# final_header.net
KiCad netlist of a schematic drawn in EAGLE
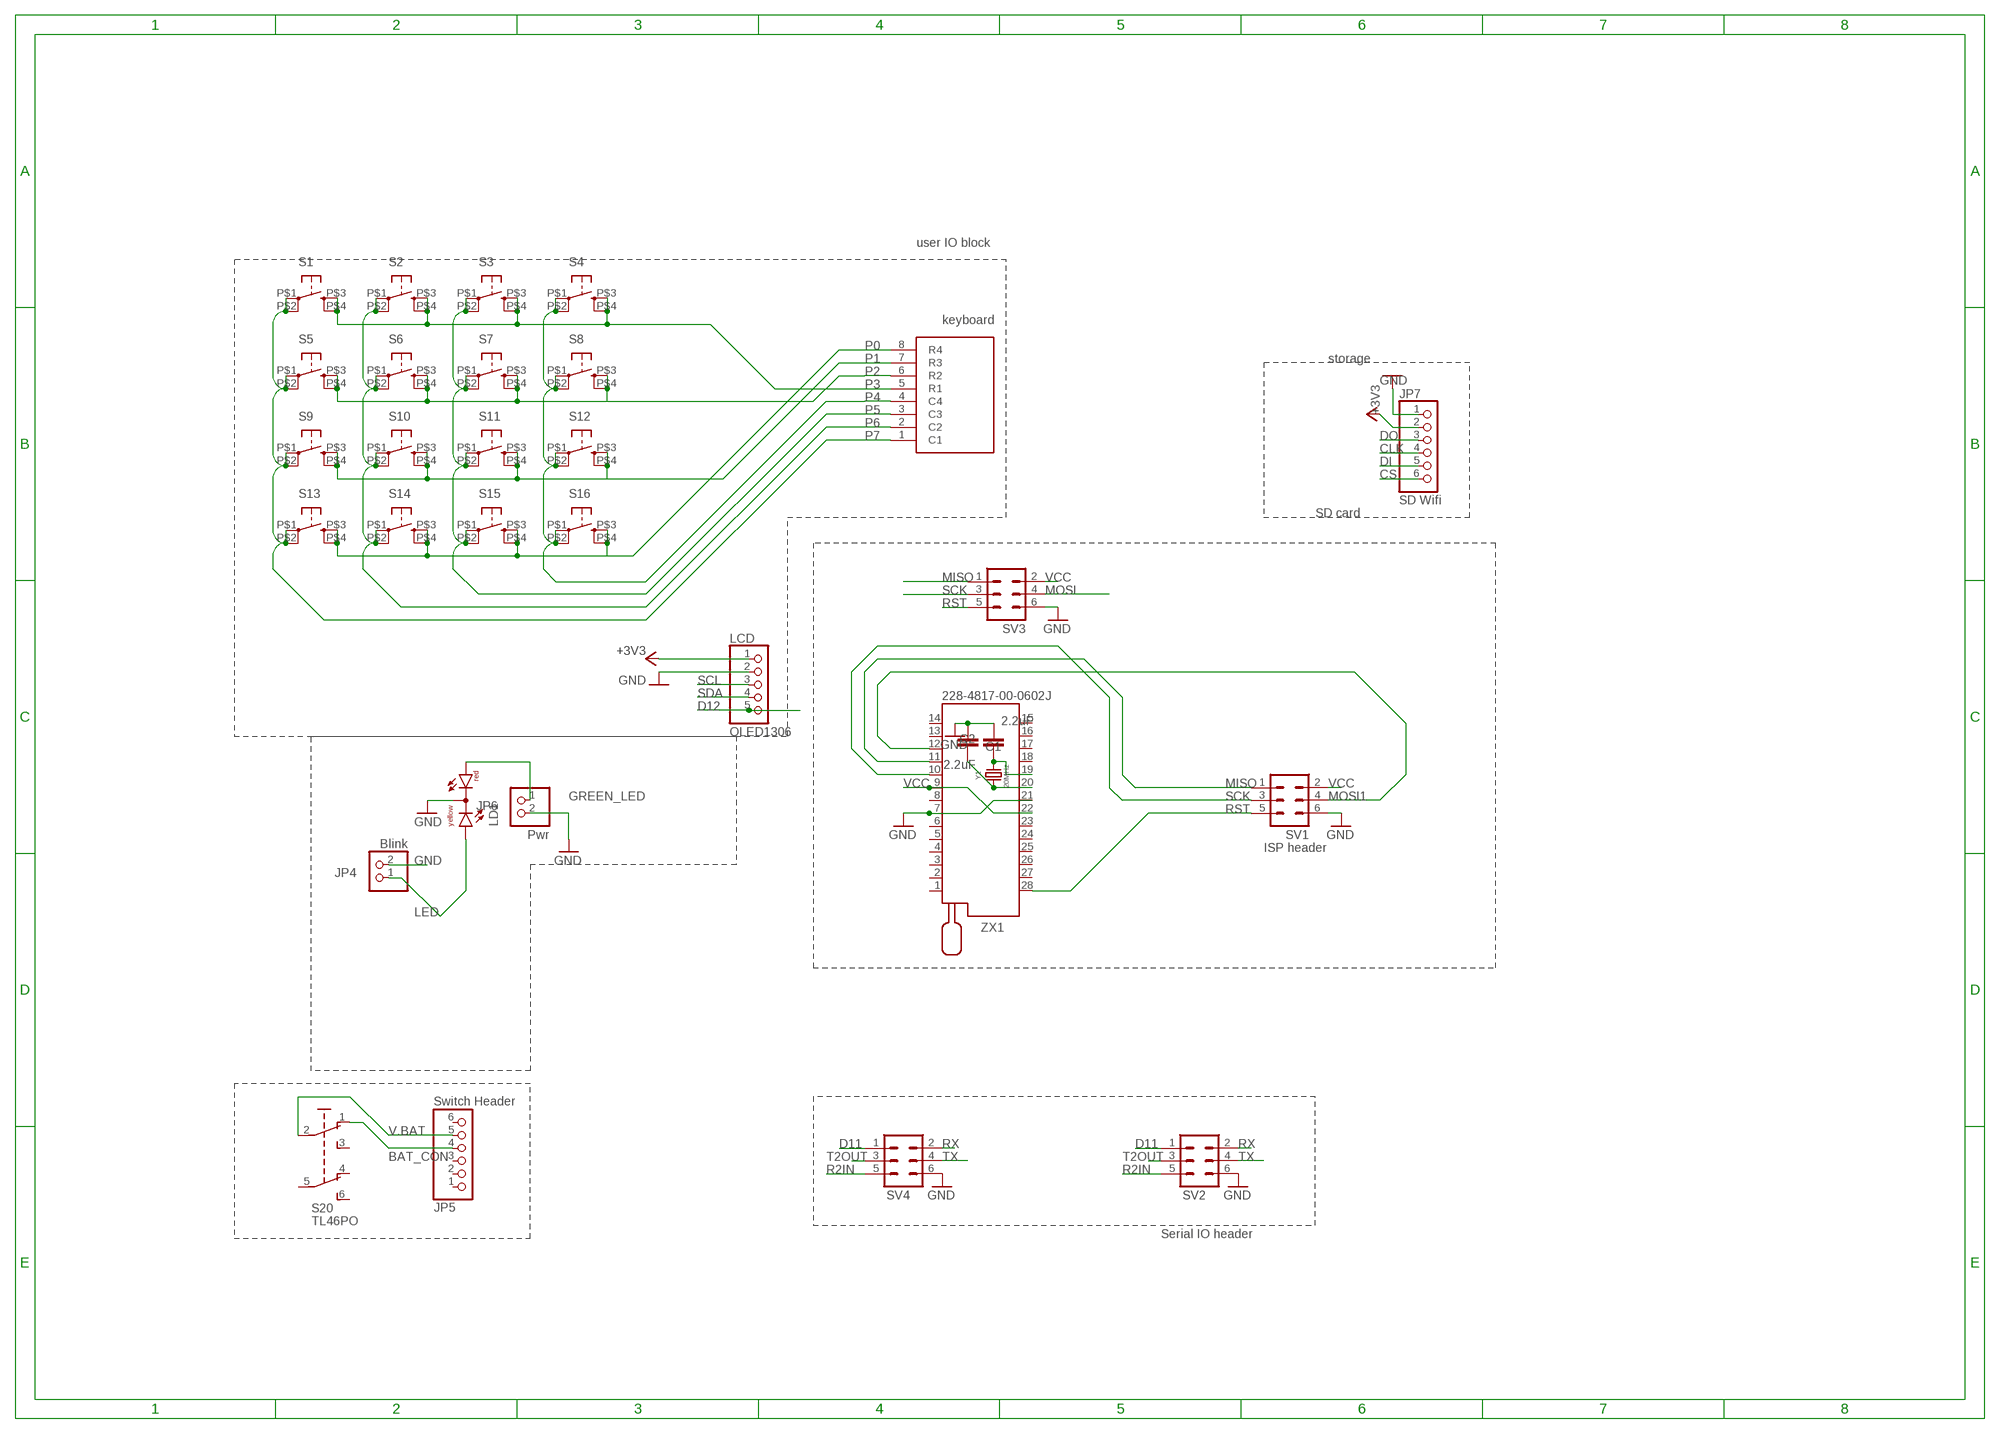
[diagram p0: schematic, sheet 1]

(export (version "E")
  (design (tool "Eeschema 10.0.6"))
  (components
    (comp (ref "C1")
      (value "2.2uF")
      (footprint "eagle-import:1206")
      (libsource (lib "eagle-import") (part "2.2UF-1206-50V-10%"))
    )
    (comp (ref "C2")
      (value "2.2uF")
      (footprint "eagle-import:1206")
      (libsource (lib "eagle-import") (part "2.2UF-1206-50V-10%"))
    )
    (comp (ref "JP4")
      (value "Blink")
      (footprint "eagle-import:1X02")
      (libsource (lib "eagle-import") (part "PINHD-1X2"))
    )
    (comp (ref "JP5")
      (value "Switch Header")
      (footprint "eagle-import:1X06")
      (libsource (lib "eagle-import") (part "PINHD-1X6"))
    )
    (comp (ref "JP6")
      (value "Pwr")
      (footprint "eagle-import:1X02")
      (libsource (lib "eagle-import") (part "PINHD-1X2"))
    )
    (comp (ref "JP7")
      (value "SD Wifi")
      (footprint "eagle-import:1X06")
      (libsource (lib "eagle-import") (part "PINHD-1X6"))
    )
    (comp (ref "LCD")
      (value "OLED1306")
      (footprint "eagle-import:1X05")
      (libsource (lib "eagle-import") (part "PINHD-1X5"))
    )
    (comp (ref "LD1")
      (value "DUOLED-RY-C")
      (footprint "eagle-import:DUOLED-C-5MM")
      (libsource (lib "eagle-import") (part "DUOLED-RY-C"))
    )
    (comp (ref "S1")
      (value "10-XX-SMD")
      (footprint "eagle-import:B3F-10XX-SMD")
      (libsource (lib "eagle-import") (part "10-XX-SMD"))
    )
    (comp (ref "S2")
      (value "10-XX-SMD")
      (footprint "eagle-import:B3F-10XX-SMD")
      (libsource (lib "eagle-import") (part "10-XX-SMD"))
    )
    (comp (ref "S3")
      (value "10-XX-SMD")
      (footprint "eagle-import:B3F-10XX-SMD")
      (libsource (lib "eagle-import") (part "10-XX-SMD"))
    )
    (comp (ref "S4")
      (value "10-XX-SMD")
      (footprint "eagle-import:B3F-10XX-SMD")
      (libsource (lib "eagle-import") (part "10-XX-SMD"))
    )
    (comp (ref "S5")
      (value "10-XX-SMD")
      (footprint "eagle-import:B3F-10XX-SMD")
      (libsource (lib "eagle-import") (part "10-XX-SMD"))
    )
    (comp (ref "S6")
      (value "10-XX-SMD")
      (footprint "eagle-import:B3F-10XX-SMD")
      (libsource (lib "eagle-import") (part "10-XX-SMD"))
    )
    (comp (ref "S7")
      (value "10-XX-SMD")
      (footprint "eagle-import:B3F-10XX-SMD")
      (libsource (lib "eagle-import") (part "10-XX-SMD"))
    )
    (comp (ref "S8")
      (value "10-XX-SMD")
      (footprint "eagle-import:B3F-10XX-SMD")
      (libsource (lib "eagle-import") (part "10-XX-SMD"))
    )
    (comp (ref "S9")
      (value "10-XX-SMD")
      (footprint "eagle-import:B3F-10XX-SMD")
      (libsource (lib "eagle-import") (part "10-XX-SMD"))
    )
    (comp (ref "S10")
      (value "10-XX-SMD")
      (footprint "eagle-import:B3F-10XX-SMD")
      (libsource (lib "eagle-import") (part "10-XX-SMD"))
    )
    (comp (ref "S11")
      (value "10-XX-SMD")
      (footprint "eagle-import:B3F-10XX-SMD")
      (libsource (lib "eagle-import") (part "10-XX-SMD"))
    )
    (comp (ref "S12")
      (value "10-XX-SMD")
      (footprint "eagle-import:B3F-10XX-SMD")
      (libsource (lib "eagle-import") (part "10-XX-SMD"))
    )
    (comp (ref "S13")
      (value "10-XX-SMD")
      (footprint "eagle-import:B3F-10XX-SMD")
      (libsource (lib "eagle-import") (part "10-XX-SMD"))
    )
    (comp (ref "S14")
      (value "10-XX-SMD")
      (footprint "eagle-import:B3F-10XX-SMD")
      (libsource (lib "eagle-import") (part "10-XX-SMD"))
    )
    (comp (ref "S15")
      (value "10-XX-SMD")
      (footprint "eagle-import:B3F-10XX-SMD")
      (libsource (lib "eagle-import") (part "10-XX-SMD"))
    )
    (comp (ref "S16")
      (value "10-XX-SMD")
      (footprint "eagle-import:B3F-10XX-SMD")
      (libsource (lib "eagle-import") (part "10-XX-SMD"))
    )
    (comp (ref "S20")
      (value "TL46PO")
      (footprint "eagle-import:TL4XPO")
      (libsource (lib "eagle-import") (part "TL46PO"))
    )
    (comp (ref "SV1")
      (value "ML6")
      (footprint "eagle-import:ML6")
      (libsource (lib "eagle-import") (part "ML6"))
    )
    (comp (ref "SV2")
      (value "ML6")
      (footprint "eagle-import:ML6")
      (libsource (lib "eagle-import") (part "ML6"))
    )
    (comp (ref "SV3")
      (value "ML6")
      (footprint "eagle-import:ML6")
      (libsource (lib "eagle-import") (part "ML6"))
    )
    (comp (ref "SV4")
      (value "ML6")
      (footprint "eagle-import:ML6")
      (libsource (lib "eagle-import") (part "ML6"))
    )
    (comp (ref "U$7")
      (value "KB1604")
      (footprint "eagle-import:KB1604")
      (libsource (lib "eagle-import") (part "KB1604"))
    )
    (comp (ref "Y1")
      (value "20MHz")
      (footprint "eagle-import:WE-XTAL_HC49_4HSMX")
      (fields (field (name "TOLERANCE") "±10ppm"))
      (libsource (lib "eagle-import") (part "WE-XTAL_HC49/4HSMX_830061856"))
    )
    (comp (ref "ZX1")
      (value "228-4817-00-0602J")
      (footprint "eagle-import:228-4817-00-0602J")
      (fields (field (name "MF") "3M"))
      (libsource (lib "eagle-import") (part "228-?00-0602J4817-"))
    )
  )
  (nets
    (net (code "1") (name "+3V3") (class "Default")
      (node (ref "JP7") (pin "2") (pinfunction "2_2") (pintype "passive"))
      (node (ref "LCD") (pin "1") (pinfunction "1_1") (pintype "passive"))
    )
    (net (code "2") (name "/BAT_CON") (class "Default")
      (node (ref "JP5") (pin "4") (pinfunction "4_4") (pintype "passive"))
      (node (ref "S20") (pin "1") (pinfunction "O_1") (pintype "passive"))
    )
    (net (code "3") (name "/CLK") (class "Default")
      (node (ref "JP7") (pin "4") (pinfunction "4_4") (pintype "passive"))
    )
    (net (code "4") (name "/CS") (class "Default")
      (node (ref "JP7") (pin "6") (pinfunction "6_6") (pintype "passive"))
    )
    (net (code "5") (name "/D11") (class "Default")
      (node (ref "SV2") (pin "1") (pinfunction "1_1") (pintype "passive"))
      (node (ref "SV4") (pin "1") (pinfunction "1_1") (pintype "passive"))
    )
    (net (code "6") (name "/D12") (class "Default")
      (node (ref "LCD") (pin "5") (pinfunction "5_5") (pintype "passive"))
    )
    (net (code "7") (name "/DI") (class "Default")
      (node (ref "JP7") (pin "5") (pinfunction "5_5") (pintype "passive"))
    )
    (net (code "8") (name "/DO") (class "Default")
      (node (ref "JP7") (pin "3") (pinfunction "3_3") (pintype "passive"))
    )
    (net (code "9") (name "/GREEN_LED") (class "Default")
      (node (ref "JP6") (pin "1") (pinfunction "1_1") (pintype "passive"))
      (node (ref "LD1") (pin "AR") (pinfunction "AR_AR") (pintype "passive"))
    )
    (net (code "10") (name "/LED") (class "Default")
      (node (ref "JP4") (pin "1") (pinfunction "1_1") (pintype "passive"))
      (node (ref "LD1") (pin "AX") (pinfunction "AY_AX") (pintype "passive"))
    )
    (net (code "11") (name "/MISO") (class "Default")
      (node (ref "SV1") (pin "1") (pinfunction "1_1") (pintype "passive"))
      (node (ref "SV3") (pin "1") (pinfunction "1_1") (pintype "passive"))
      (node (ref "ZX1") (pin "11") (pinfunction "11_11") (pintype "passive"))
    )
    (net (code "12") (name "/MOSI") (class "Default")
      (node (ref "SV3") (pin "4") (pinfunction "4_4") (pintype "passive"))
    )
    (net (code "13") (name "/MOSI1") (class "Default")
      (node (ref "SV1") (pin "4") (pinfunction "4_4") (pintype "passive"))
      (node (ref "ZX1") (pin "12") (pinfunction "12_12") (pintype "passive"))
    )
    (net (code "14") (name "/P0") (class "Default")
      (node (ref "S13") (pin "P$3") (pinfunction "S_P$3") (pintype "passive"))
      (node (ref "S13") (pin "P$4") (pinfunction "S1_P$4") (pintype "passive"))
      (node (ref "S14") (pin "P$3") (pinfunction "S_P$3") (pintype "passive"))
      (node (ref "S14") (pin "P$4") (pinfunction "S1_P$4") (pintype "passive"))
      (node (ref "S15") (pin "P$3") (pinfunction "S_P$3") (pintype "passive"))
      (node (ref "S15") (pin "P$4") (pinfunction "S1_P$4") (pintype "passive"))
      (node (ref "S16") (pin "P$3") (pinfunction "S_P$3") (pintype "passive"))
      (node (ref "S16") (pin "P$4") (pinfunction "S1_P$4") (pintype "passive"))
      (node (ref "U$7") (pin "8") (pinfunction "R4_8") (pintype "bidirectional"))
    )
    (net (code "15") (name "/P1") (class "Default")
      (node (ref "U$7") (pin "7") (pinfunction "R3_7") (pintype "bidirectional"))
    )
    (net (code "16") (name "/P2") (class "Default")
      (node (ref "S5") (pin "P$3") (pinfunction "S_P$3") (pintype "passive"))
      (node (ref "S5") (pin "P$4") (pinfunction "S1_P$4") (pintype "passive"))
      (node (ref "S6") (pin "P$3") (pinfunction "S_P$3") (pintype "passive"))
      (node (ref "S6") (pin "P$4") (pinfunction "S1_P$4") (pintype "passive"))
      (node (ref "S7") (pin "P$3") (pinfunction "S_P$3") (pintype "passive"))
      (node (ref "S7") (pin "P$4") (pinfunction "S1_P$4") (pintype "passive"))
      (node (ref "S8") (pin "P$3") (pinfunction "S_P$3") (pintype "passive"))
      (node (ref "S8") (pin "P$4") (pinfunction "S1_P$4") (pintype "passive"))
      (node (ref "U$7") (pin "6") (pinfunction "R2_6") (pintype "bidirectional"))
    )
    (net (code "17") (name "/P3") (class "Default")
      (node (ref "S1") (pin "P$3") (pinfunction "S_P$3") (pintype "passive"))
      (node (ref "S1") (pin "P$4") (pinfunction "S1_P$4") (pintype "passive"))
      (node (ref "S2") (pin "P$3") (pinfunction "S_P$3") (pintype "passive"))
      (node (ref "S2") (pin "P$4") (pinfunction "S1_P$4") (pintype "passive"))
      (node (ref "S3") (pin "P$3") (pinfunction "S_P$3") (pintype "passive"))
      (node (ref "S3") (pin "P$4") (pinfunction "S1_P$4") (pintype "passive"))
      (node (ref "S4") (pin "P$3") (pinfunction "S_P$3") (pintype "passive"))
      (node (ref "S4") (pin "P$4") (pinfunction "S1_P$4") (pintype "passive"))
      (node (ref "U$7") (pin "5") (pinfunction "R1_5") (pintype "bidirectional"))
    )
    (net (code "18") (name "/P4") (class "Default")
      (node (ref "S12") (pin "P$1") (pinfunction "P_P$1") (pintype "passive"))
      (node (ref "S12") (pin "P$2") (pinfunction "P1_P$2") (pintype "passive"))
      (node (ref "S16") (pin "P$1") (pinfunction "P_P$1") (pintype "passive"))
      (node (ref "S16") (pin "P$2") (pinfunction "P1_P$2") (pintype "passive"))
      (node (ref "S4") (pin "P$1") (pinfunction "P_P$1") (pintype "passive"))
      (node (ref "S4") (pin "P$2") (pinfunction "P1_P$2") (pintype "passive"))
      (node (ref "S8") (pin "P$1") (pinfunction "P_P$1") (pintype "passive"))
      (node (ref "S8") (pin "P$2") (pinfunction "P1_P$2") (pintype "passive"))
      (node (ref "U$7") (pin "4") (pinfunction "C4_4") (pintype "bidirectional"))
    )
    (net (code "19") (name "/P5") (class "Default")
      (node (ref "S11") (pin "P$1") (pinfunction "P_P$1") (pintype "passive"))
      (node (ref "S11") (pin "P$2") (pinfunction "P1_P$2") (pintype "passive"))
      (node (ref "S15") (pin "P$1") (pinfunction "P_P$1") (pintype "passive"))
      (node (ref "S15") (pin "P$2") (pinfunction "P1_P$2") (pintype "passive"))
      (node (ref "S3") (pin "P$1") (pinfunction "P_P$1") (pintype "passive"))
      (node (ref "S3") (pin "P$2") (pinfunction "P1_P$2") (pintype "passive"))
      (node (ref "S7") (pin "P$1") (pinfunction "P_P$1") (pintype "passive"))
      (node (ref "S7") (pin "P$2") (pinfunction "P1_P$2") (pintype "passive"))
      (node (ref "U$7") (pin "3") (pinfunction "C3_3") (pintype "bidirectional"))
    )
    (net (code "20") (name "/P6") (class "Default")
      (node (ref "S10") (pin "P$1") (pinfunction "P_P$1") (pintype "passive"))
      (node (ref "S10") (pin "P$2") (pinfunction "P1_P$2") (pintype "passive"))
      (node (ref "S14") (pin "P$1") (pinfunction "P_P$1") (pintype "passive"))
      (node (ref "S14") (pin "P$2") (pinfunction "P1_P$2") (pintype "passive"))
      (node (ref "S2") (pin "P$1") (pinfunction "P_P$1") (pintype "passive"))
      (node (ref "S2") (pin "P$2") (pinfunction "P1_P$2") (pintype "passive"))
      (node (ref "S6") (pin "P$1") (pinfunction "P_P$1") (pintype "passive"))
      (node (ref "S6") (pin "P$2") (pinfunction "P1_P$2") (pintype "passive"))
      (node (ref "U$7") (pin "2") (pinfunction "C2_2") (pintype "bidirectional"))
    )
    (net (code "21") (name "/P7") (class "Default")
      (node (ref "S1") (pin "P$1") (pinfunction "P_P$1") (pintype "passive"))
      (node (ref "S1") (pin "P$2") (pinfunction "P1_P$2") (pintype "passive"))
      (node (ref "S13") (pin "P$1") (pinfunction "P_P$1") (pintype "passive"))
      (node (ref "S13") (pin "P$2") (pinfunction "P1_P$2") (pintype "passive"))
      (node (ref "S5") (pin "P$1") (pinfunction "P_P$1") (pintype "passive"))
      (node (ref "S5") (pin "P$2") (pinfunction "P1_P$2") (pintype "passive"))
      (node (ref "S9") (pin "P$1") (pinfunction "P_P$1") (pintype "passive"))
      (node (ref "S9") (pin "P$2") (pinfunction "P1_P$2") (pintype "passive"))
      (node (ref "U$7") (pin "1") (pinfunction "C1_1") (pintype "bidirectional"))
    )
    (net (code "22") (name "/R2IN") (class "Default")
      (node (ref "SV2") (pin "5") (pinfunction "5_5") (pintype "passive"))
      (node (ref "SV4") (pin "5") (pinfunction "5_5") (pintype "passive"))
    )
    (net (code "23") (name "/RST") (class "Default")
      (node (ref "SV1") (pin "5") (pinfunction "5_5") (pintype "passive"))
      (node (ref "SV3") (pin "5") (pinfunction "5_5") (pintype "passive"))
      (node (ref "ZX1") (pin "28") (pinfunction "28_28") (pintype "passive"))
    )
    (net (code "24") (name "/RX") (class "Default")
      (node (ref "SV2") (pin "2") (pinfunction "2_2") (pintype "passive"))
      (node (ref "SV4") (pin "2") (pinfunction "2_2") (pintype "passive"))
    )
    (net (code "25") (name "/SCK") (class "Default")
      (node (ref "SV1") (pin "3") (pinfunction "3_3") (pintype "passive"))
      (node (ref "SV3") (pin "3") (pinfunction "3_3") (pintype "passive"))
      (node (ref "ZX1") (pin "10") (pinfunction "10_10") (pintype "passive"))
    )
    (net (code "26") (name "/SCL") (class "Default")
      (node (ref "LCD") (pin "3") (pinfunction "3_3") (pintype "passive"))
    )
    (net (code "27") (name "/SDA") (class "Default")
      (node (ref "LCD") (pin "4") (pinfunction "4_4") (pintype "passive"))
    )
    (net (code "28") (name "/T2OUT") (class "Default")
      (node (ref "SV2") (pin "3") (pinfunction "3_3") (pintype "passive"))
      (node (ref "SV4") (pin "3") (pinfunction "3_3") (pintype "passive"))
    )
    (net (code "29") (name "/TX") (class "Default")
      (node (ref "SV2") (pin "4") (pinfunction "4_4") (pintype "passive"))
      (node (ref "SV4") (pin "4") (pinfunction "4_4") (pintype "passive"))
    )
    (net (code "30") (name "/V.BAT") (class "Default")
      (node (ref "JP5") (pin "5") (pinfunction "5_5") (pintype "passive"))
      (node (ref "S20") (pin "2") (pinfunction "P_2") (pintype "passive"))
    )
    (net (code "31") (name "/VCC") (class "Default")
      (node (ref "SV1") (pin "2") (pinfunction "2_2") (pintype "passive"))
      (node (ref "SV3") (pin "2") (pinfunction "2_2") (pintype "passive"))
      (node (ref "ZX1") (pin "22") (pinfunction "22_22") (pintype "passive"))
      (node (ref "ZX1") (pin "9") (pinfunction "9_9") (pintype "passive"))
    )
    (net (code "32") (name "GND") (class "Default")
      (node (ref "C1") (pin "2") (pinfunction "2_2") (pintype "passive"))
      (node (ref "C2") (pin "1") (pinfunction "1_1") (pintype "passive"))
      (node (ref "JP4") (pin "2") (pinfunction "2_2") (pintype "passive"))
      (node (ref "JP6") (pin "2") (pinfunction "2_2") (pintype "passive"))
      (node (ref "JP7") (pin "1") (pinfunction "1_1") (pintype "passive"))
      (node (ref "LCD") (pin "2") (pinfunction "2_2") (pintype "passive"))
      (node (ref "LD1") (pin "C") (pinfunction "C_C") (pintype "passive"))
      (node (ref "SV1") (pin "6") (pinfunction "6_6") (pintype "passive"))
      (node (ref "SV2") (pin "6") (pinfunction "6_6") (pintype "passive"))
      (node (ref "SV3") (pin "6") (pinfunction "6_6") (pintype "passive"))
      (node (ref "SV4") (pin "6") (pinfunction "6_6") (pintype "passive"))
      (node (ref "ZX1") (pin "21") (pinfunction "21_21") (pintype "passive"))
      (node (ref "ZX1") (pin "7") (pinfunction "7_7") (pintype "passive"))
    )
    (net (code "33") (name "Net-(C1-Pad1)") (class "Default")
      (node (ref "C1") (pin "1") (pinfunction "1_1") (pintype "passive"))
      (node (ref "Y1") (pin "2") (pinfunction "2_2") (pintype "passive"))
      (node (ref "ZX1") (pin "19") (pinfunction "19_19") (pintype "passive"))
    )
    (net (code "34") (name "Net-(C2-Pad2)") (class "Default")
      (node (ref "C2") (pin "2") (pinfunction "2_2") (pintype "passive"))
      (node (ref "Y1") (pin "1") (pinfunction "1_1") (pintype "passive"))
      (node (ref "ZX1") (pin "20") (pinfunction "20_20") (pintype "passive"))
    )
    (net (code "35") (name "Net-(S10-S)") (class "Default")
      (node (ref "S10") (pin "P$3") (pinfunction "S_P$3") (pintype "passive"))
      (node (ref "S10") (pin "P$4") (pinfunction "S1_P$4") (pintype "passive"))
      (node (ref "S11") (pin "P$3") (pinfunction "S_P$3") (pintype "passive"))
      (node (ref "S11") (pin "P$4") (pinfunction "S1_P$4") (pintype "passive"))
      (node (ref "S12") (pin "P$3") (pinfunction "S_P$3") (pintype "passive"))
      (node (ref "S12") (pin "P$4") (pinfunction "S1_P$4") (pintype "passive"))
      (node (ref "S9") (pin "P$3") (pinfunction "S_P$3") (pintype "passive"))
      (node (ref "S9") (pin "P$4") (pinfunction "S1_P$4") (pintype "passive"))
    )
    (net (code "36") (name "unconnected-(JP5-Pad1)") (class "Default")
      (node (ref "JP5") (pin "1") (pinfunction "1_1") (pintype "passive"))
    )
    (net (code "37") (name "unconnected-(JP5-Pad2)") (class "Default")
      (node (ref "JP5") (pin "2") (pinfunction "2_2") (pintype "passive"))
    )
    (net (code "38") (name "unconnected-(JP5-Pad3)") (class "Default")
      (node (ref "JP5") (pin "3") (pinfunction "3_3") (pintype "passive"))
    )
    (net (code "39") (name "unconnected-(JP5-Pad6)") (class "Default")
      (node (ref "JP5") (pin "6") (pinfunction "6_6") (pintype "passive"))
    )
    (net (code "40") (name "unconnected-(S20-O1-Pad4)") (class "Default")
      (node (ref "S20") (pin "4") (pinfunction "O1_4") (pintype "passive"))
    )
    (net (code "41") (name "unconnected-(S20-P1-Pad5)") (class "Default")
      (node (ref "S20") (pin "5") (pinfunction "P1_5") (pintype "passive"))
    )
    (net (code "42") (name "unconnected-(S20-S-Pad3)") (class "Default")
      (node (ref "S20") (pin "3") (pinfunction "S_3") (pintype "passive"))
    )
    (net (code "43") (name "unconnected-(S20-S1-Pad6)") (class "Default")
      (node (ref "S20") (pin "6") (pinfunction "S1_6") (pintype "passive"))
    )
    (net (code "44") (name "unconnected-(ZX1-Pad1)") (class "Default")
      (node (ref "ZX1") (pin "1") (pinfunction "1_1") (pintype "passive"))
    )
    (net (code "45") (name "unconnected-(ZX1-Pad2)") (class "Default")
      (node (ref "ZX1") (pin "2") (pinfunction "2_2") (pintype "passive"))
    )
    (net (code "46") (name "unconnected-(ZX1-Pad3)") (class "Default")
      (node (ref "ZX1") (pin "3") (pinfunction "3_3") (pintype "passive"))
    )
    (net (code "47") (name "unconnected-(ZX1-Pad4)") (class "Default")
      (node (ref "ZX1") (pin "4") (pinfunction "4_4") (pintype "passive"))
    )
    (net (code "48") (name "unconnected-(ZX1-Pad5)") (class "Default")
      (node (ref "ZX1") (pin "5") (pinfunction "5_5") (pintype "passive"))
    )
    (net (code "49") (name "unconnected-(ZX1-Pad6)") (class "Default")
      (node (ref "ZX1") (pin "6") (pinfunction "6_6") (pintype "passive"))
    )
    (net (code "50") (name "unconnected-(ZX1-Pad8)") (class "Default")
      (node (ref "ZX1") (pin "8") (pinfunction "8_8") (pintype "passive"))
    )
    (net (code "51") (name "unconnected-(ZX1-Pad13)") (class "Default")
      (node (ref "ZX1") (pin "13") (pinfunction "13_13") (pintype "passive"))
    )
    (net (code "52") (name "unconnected-(ZX1-Pad14)") (class "Default")
      (node (ref "ZX1") (pin "14") (pinfunction "14_14") (pintype "passive"))
    )
    (net (code "53") (name "unconnected-(ZX1-Pad15)") (class "Default")
      (node (ref "ZX1") (pin "15") (pinfunction "15_15") (pintype "passive"))
    )
    (net (code "54") (name "unconnected-(ZX1-Pad16)") (class "Default")
      (node (ref "ZX1") (pin "16") (pinfunction "16_16") (pintype "passive"))
    )
    (net (code "55") (name "unconnected-(ZX1-Pad17)") (class "Default")
      (node (ref "ZX1") (pin "17") (pinfunction "17_17") (pintype "passive"))
    )
    (net (code "56") (name "unconnected-(ZX1-Pad18)") (class "Default")
      (node (ref "ZX1") (pin "18") (pinfunction "18_18") (pintype "passive"))
    )
    (net (code "57") (name "unconnected-(ZX1-Pad23)") (class "Default")
      (node (ref "ZX1") (pin "23") (pinfunction "23_23") (pintype "passive"))
    )
    (net (code "58") (name "unconnected-(ZX1-Pad24)") (class "Default")
      (node (ref "ZX1") (pin "24") (pinfunction "24_24") (pintype "passive"))
    )
    (net (code "59") (name "unconnected-(ZX1-Pad25)") (class "Default")
      (node (ref "ZX1") (pin "25") (pinfunction "25_25") (pintype "passive"))
    )
    (net (code "60") (name "unconnected-(ZX1-Pad26)") (class "Default")
      (node (ref "ZX1") (pin "26") (pinfunction "26_26") (pintype "passive"))
    )
    (net (code "61") (name "unconnected-(ZX1-Pad27)") (class "Default")
      (node (ref "ZX1") (pin "27") (pinfunction "27_27") (pintype "passive"))
    )
  )
)
